# mcu0_to_mcu1_isolated_SPI.net
KiCad netlist of a schematic drawn in Altium Designer
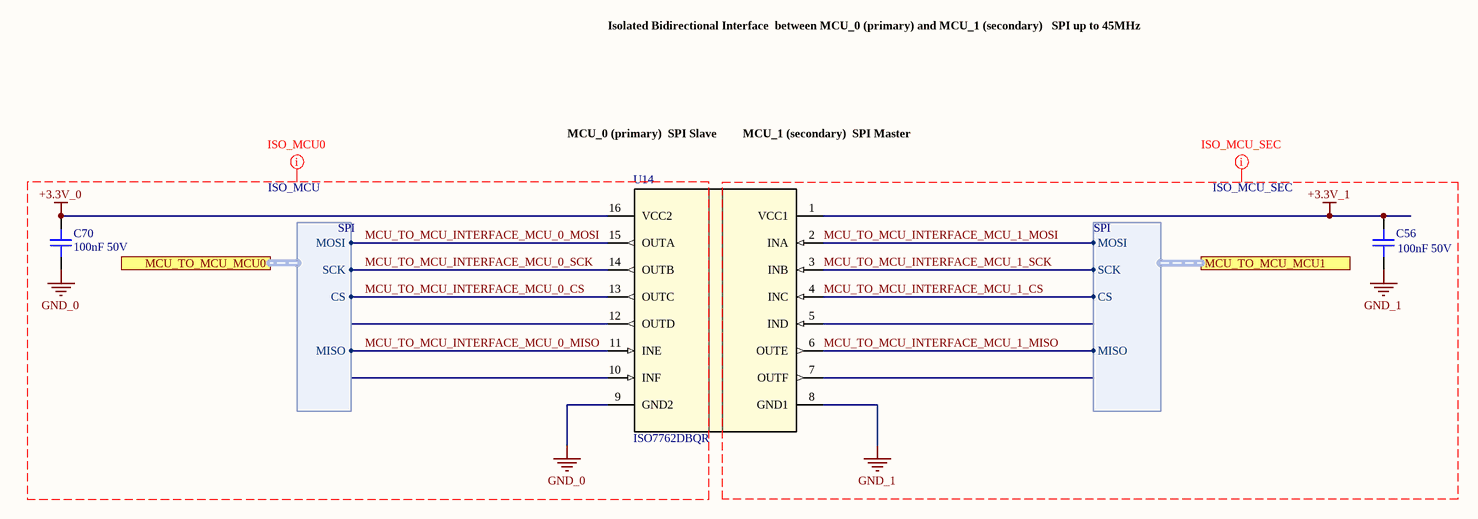
[diagram p0: mcu0_to_mcu1_isolated_SPI.SchDoc]

(export (version "E")
  (design (tool "Eeschema 10.0.6"))
  (components
    (comp (ref "C56")
      (value "100nF 50V")
      (footprint "0603C")
      (description "Ceramic, 100nF, ±10%, 50V, X7R, –55 to 125°C, 0603 (1608),RoHS, Automotive")
      (fields (field (name "PART NUMBER") "GCJ188R71H104KA12") (field (name "TOLERANCE") "±10%"))
      (libsource (lib "master-010106") (part "C"))
    )
    (comp (ref "C70")
      (value "100nF 50V")
      (footprint "0603C")
      (description "Ceramic, 100nF, ±10%, 50V, X7R, –55 to 125°C, 0603 (1608),RoHS, Automotive")
      (fields (field (name "PART NUMBER") "GCJ188R71H104KA12") (field (name "TOLERANCE") "±10%"))
      (libsource (lib "master-010106") (part "C"))
    )
    (comp (ref "U14")
      (value "ISO7762DBQR")
      (footprint "DBQ0016A_N")
      (description "Imported")
      (fields (field (name "MANUFACTURER") "Texas Instruments") (field (name "PARTNUMBER") "ISO7760DBQR"))
      (libsource (lib "ti-import") (part "ISO7762DBQR"))
    )
  )
  (nets
    (net (code "2") (name "+3.3V_0") (class "Default")
      (node (ref "C70") (pin "2") (pinfunction "2_2") (pintype "passive"))
      (node (ref "U14") (pin "16") (pinfunction "VCC2_16") (pintype "power_in"))
    )
    (net (code "3") (name "+3.3V_1") (class "Default")
      (node (ref "C56") (pin "1") (pinfunction "1_1") (pintype "passive"))
      (node (ref "U14") (pin "1") (pinfunction "VCC1_1") (pintype "power_in"))
    )
    (net (code "4") (name "/MCU_TO_MCU_INTERFACE_MCU_0_CS") (class "Default")
      (node (ref "U14") (pin "13") (pinfunction "OUTC_13") (pintype "output"))
    )
    (net (code "5") (name "/MCU_TO_MCU_INTERFACE_MCU_0_MISO") (class "Default")
      (node (ref "U14") (pin "11") (pinfunction "INE_11") (pintype "input"))
    )
    (net (code "6") (name "/MCU_TO_MCU_INTERFACE_MCU_0_MOSI") (class "Default")
      (node (ref "U14") (pin "15") (pinfunction "OUTA_15") (pintype "output"))
    )
    (net (code "7") (name "/MCU_TO_MCU_INTERFACE_MCU_0_SCK") (class "Default")
      (node (ref "U14") (pin "14") (pinfunction "OUTB_14") (pintype "output"))
    )
    (net (code "8") (name "/MCU_TO_MCU_INTERFACE_MCU_1_CS") (class "Default")
      (node (ref "U14") (pin "4") (pinfunction "INC_4") (pintype "input"))
    )
    (net (code "9") (name "/MCU_TO_MCU_INTERFACE_MCU_1_MISO") (class "Default")
      (node (ref "U14") (pin "6") (pinfunction "OUTE_6") (pintype "output"))
    )
    (net (code "10") (name "/MCU_TO_MCU_INTERFACE_MCU_1_MOSI") (class "Default")
      (node (ref "U14") (pin "2") (pinfunction "INA_2") (pintype "input"))
    )
    (net (code "11") (name "/MCU_TO_MCU_INTERFACE_MCU_1_SCK") (class "Default")
      (node (ref "U14") (pin "3") (pinfunction "INB_3") (pintype "input"))
    )
    (net (code "13") (name "GND_0") (class "Default")
      (node (ref "C70") (pin "1") (pinfunction "1_1") (pintype "passive"))
      (node (ref "U14") (pin "9") (pinfunction "GND2_9") (pintype "power_in"))
    )
    (net (code "14") (name "GND_1") (class "Default")
      (node (ref "C56") (pin "2") (pinfunction "2_2") (pintype "passive"))
      (node (ref "U14") (pin "8") (pinfunction "GND1_8") (pintype "power_in"))
    )
    (net (code "15") (name "unconnected-(U14-IND-Pad5)") (class "Default")
      (node (ref "U14") (pin "5") (pinfunction "IND_5") (pintype "input"))
    )
    (net (code "16") (name "unconnected-(U14-INF-Pad10)") (class "Default")
      (node (ref "U14") (pin "10") (pinfunction "INF_10") (pintype "input"))
    )
    (net (code "17") (name "unconnected-(U14-OUTD-Pad12)") (class "Default")
      (node (ref "U14") (pin "12") (pinfunction "OUTD_12") (pintype "output"))
    )
    (net (code "18") (name "unconnected-(U14-OUTF-Pad7)") (class "Default")
      (node (ref "U14") (pin "7") (pinfunction "OUTF_7") (pintype "output"))
    )
  )
)
